# og-hello.net
KiCad netlist of a schematic drawn in EAGLE
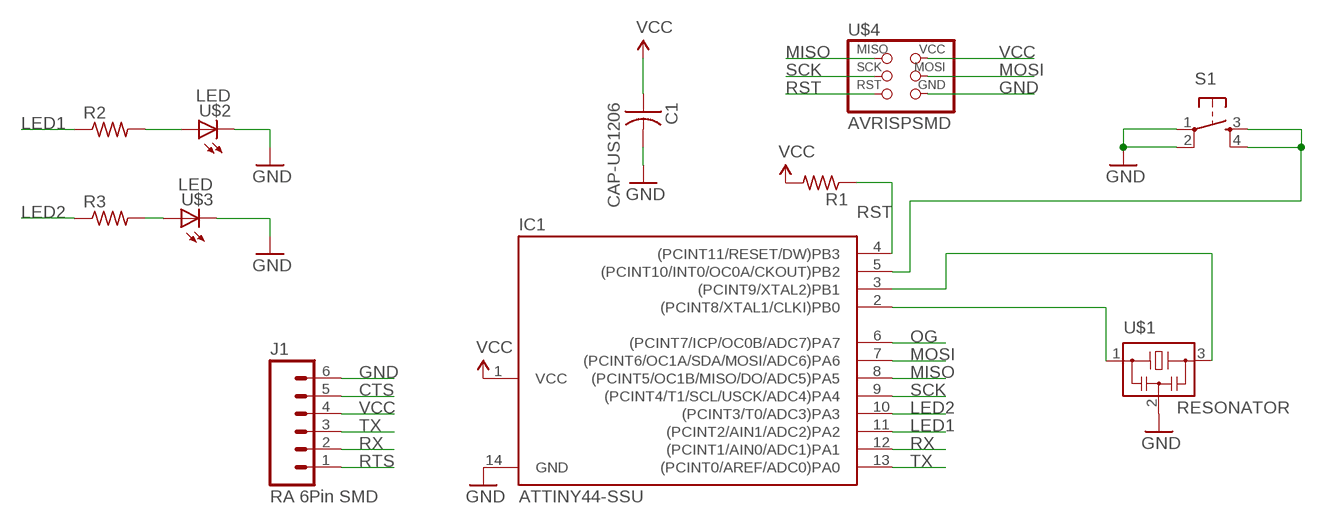
[diagram p0: schematic, sheet 1]

(export (version "E")
  (design (tool "Eeschema 10.0.6"))
  (components
    (comp (ref "C1")
      (value "CAP-US1206")
      (footprint "eagle-import:C1206")
      (libsource (lib "eagle-import") (part "CAP-US1206"))
    )
    (comp (ref "IC1")
      (value "ATTINY44-SSU")
      (footprint "eagle-import:SOIC14")
      (libsource (lib "eagle-import") (part "ATTINY44-SSU"))
    )
    (comp (ref "J1")
      (value "RA 6Pin SMD")
      (footprint "eagle-import:1X06-SMD")
      (libsource (lib "eagle-import") (part "M06SMD"))
    )
    (comp (ref "R1")
      (value "RES-US1206")
      (footprint "eagle-import:R1206")
      (libsource (lib "eagle-import") (part "RES-US1206"))
    )
    (comp (ref "R2")
      (value "RES-US1206")
      (footprint "eagle-import:R1206")
      (libsource (lib "eagle-import") (part "RES-US1206"))
    )
    (comp (ref "R3")
      (value "RES-US1206")
      (footprint "eagle-import:R1206")
      (libsource (lib "eagle-import") (part "RES-US1206"))
    )
    (comp (ref "S1")
      (value "6MM_SWITCH6MM_SWITCH")
      (footprint "eagle-import:6MM_SWITCH")
      (libsource (lib "eagle-import") (part "6MM_SWITCH6MM_SWITCH"))
    )
    (comp (ref "U$1")
      (value "RESONATOR")
      (footprint "eagle-import:EFOBM")
      (libsource (lib "eagle-import") (part "RESONATOR"))
    )
    (comp (ref "U$2")
      (value "LED")
      (footprint "eagle-import:LED1206")
      (libsource (lib "eagle-import") (part "LED"))
    )
    (comp (ref "U$3")
      (value "LED")
      (footprint "eagle-import:LED1206")
      (libsource (lib "eagle-import") (part "LED"))
    )
    (comp (ref "U$4")
      (value "AVRISPSMD")
      (footprint "eagle-import:2X03SMD")
      (libsource (lib "eagle-import") (part "AVRISPSMD"))
    )
  )
  (nets
    (net (code "1") (name "/CTS") (class "Default")
      (node (ref "J1") (pin "5") (pinfunction "5_5") (pintype "passive"))
    )
    (net (code "2") (name "/LED1") (class "Default")
      (node (ref "IC1") (pin "11") (pinfunction "(PCINT2/AIN1/ADC2)PA2_11") (pintype "bidirectional"))
      (node (ref "R2") (pin "1") (pinfunction "1_1") (pintype "passive"))
    )
    (net (code "3") (name "/LED2") (class "Default")
      (node (ref "IC1") (pin "10") (pinfunction "(PCINT3/T0/ADC3)PA3_10") (pintype "bidirectional"))
      (node (ref "R3") (pin "1") (pinfunction "1_1") (pintype "passive"))
    )
    (net (code "4") (name "/MISO") (class "Default")
      (node (ref "IC1") (pin "8") (pinfunction "(PCINT5/OC1B/MISO/DO/ADC5)PA5_8") (pintype "bidirectional"))
      (node (ref "U$4") (pin "1") (pinfunction "MISO_1") (pintype "passive"))
    )
    (net (code "5") (name "/MOSI") (class "Default")
      (node (ref "IC1") (pin "7") (pinfunction "(PCINT6/OC1A/SDA/MOSI/ADC6)PA6_7") (pintype "bidirectional"))
      (node (ref "U$4") (pin "4") (pinfunction "MOSI_4") (pintype "passive"))
    )
    (net (code "6") (name "/OG") (class "Default")
      (node (ref "IC1") (pin "6") (pinfunction "(PCINT7/ICP/OC0B/ADC7)PA7_6") (pintype "bidirectional"))
    )
    (net (code "7") (name "/RST") (class "Default")
      (node (ref "IC1") (pin "4") (pinfunction "(PCINT11/RESET/DW)PB3_4") (pintype "bidirectional"))
      (node (ref "R1") (pin "1") (pinfunction "1_1") (pintype "passive"))
      (node (ref "U$4") (pin "5") (pinfunction "RST_5") (pintype "passive"))
    )
    (net (code "8") (name "/RTS") (class "Default")
      (node (ref "J1") (pin "1") (pinfunction "1_1") (pintype "passive"))
    )
    (net (code "9") (name "/RX") (class "Default")
      (node (ref "IC1") (pin "12") (pinfunction "(PCINT1/AIN0/ADC1)PA1_12") (pintype "bidirectional"))
      (node (ref "J1") (pin "2") (pinfunction "2_2") (pintype "passive"))
    )
    (net (code "10") (name "/SCK") (class "Default")
      (node (ref "IC1") (pin "9") (pinfunction "(PCINT4/T1/SCL/USCK/ADC4)PA4_9") (pintype "bidirectional"))
      (node (ref "U$4") (pin "3") (pinfunction "SCK_3") (pintype "passive"))
    )
    (net (code "11") (name "/TX") (class "Default")
      (node (ref "IC1") (pin "13") (pinfunction "(PCINT0/AREF/ADC0)PA0_13") (pintype "bidirectional"))
      (node (ref "J1") (pin "3") (pinfunction "3_3") (pintype "passive"))
    )
    (net (code "12") (name "GND") (class "Default")
      (node (ref "C1") (pin "2") (pinfunction "2_2") (pintype "passive"))
      (node (ref "IC1") (pin "14") (pinfunction "GND_14") (pintype "power_in"))
      (node (ref "J1") (pin "6") (pinfunction "6_6") (pintype "passive"))
      (node (ref "S1") (pin "1") (pinfunction "P_1") (pintype "passive"))
      (node (ref "S1") (pin "2") (pinfunction "P1_2") (pintype "passive"))
      (node (ref "U$1") (pin "2") (pinfunction "2_2") (pintype "passive"))
      (node (ref "U$2") (pin "2") (pinfunction "C_2") (pintype "passive"))
      (node (ref "U$3") (pin "2") (pinfunction "C_2") (pintype "passive"))
      (node (ref "U$4") (pin "6") (pinfunction "GND_6") (pintype "passive"))
    )
    (net (code "13") (name "Net-(IC1-(PCINT8{slash}XTAL1{slash}CLKI)PB0)") (class "Default")
      (node (ref "IC1") (pin "2") (pinfunction "(PCINT8/XTAL1/CLKI)PB0_2") (pintype "bidirectional"))
      (node (ref "U$1") (pin "1") (pinfunction "1_1") (pintype "passive"))
    )
    (net (code "14") (name "Net-(IC1-(PCINT9{slash}XTAL2)PB1)") (class "Default")
      (node (ref "IC1") (pin "3") (pinfunction "(PCINT9/XTAL2)PB1_3") (pintype "bidirectional"))
      (node (ref "U$1") (pin "3") (pinfunction "3_3") (pintype "passive"))
    )
    (net (code "15") (name "Net-(IC1-(PCINT10{slash}INT0{slash}OC0A{slash}CKOUT)PB2)") (class "Default")
      (node (ref "IC1") (pin "5") (pinfunction "(PCINT10/INT0/OC0A/CKOUT)PB2_5") (pintype "bidirectional"))
      (node (ref "S1") (pin "3") (pinfunction "S_3") (pintype "passive"))
      (node (ref "S1") (pin "4") (pinfunction "S1_4") (pintype "passive"))
    )
    (net (code "16") (name "Net-(U$2-A)") (class "Default")
      (node (ref "R2") (pin "2") (pinfunction "2_2") (pintype "passive"))
      (node (ref "U$2") (pin "1") (pinfunction "A_1") (pintype "passive"))
    )
    (net (code "17") (name "Net-(U$3-A)") (class "Default")
      (node (ref "R3") (pin "2") (pinfunction "2_2") (pintype "passive"))
      (node (ref "U$3") (pin "1") (pinfunction "A_1") (pintype "passive"))
    )
    (net (code "18") (name "VCC") (class "Default")
      (node (ref "C1") (pin "1") (pinfunction "1_1") (pintype "passive"))
      (node (ref "IC1") (pin "1") (pinfunction "VCC_1") (pintype "power_in"))
      (node (ref "J1") (pin "4") (pinfunction "4_4") (pintype "passive"))
      (node (ref "R1") (pin "2") (pinfunction "2_2") (pintype "passive"))
      (node (ref "U$4") (pin "2") (pinfunction "VCC_2") (pintype "passive"))
    )
  )
)
